# untitled.net
KiCad netlist of a schematic drawn in EAGLE
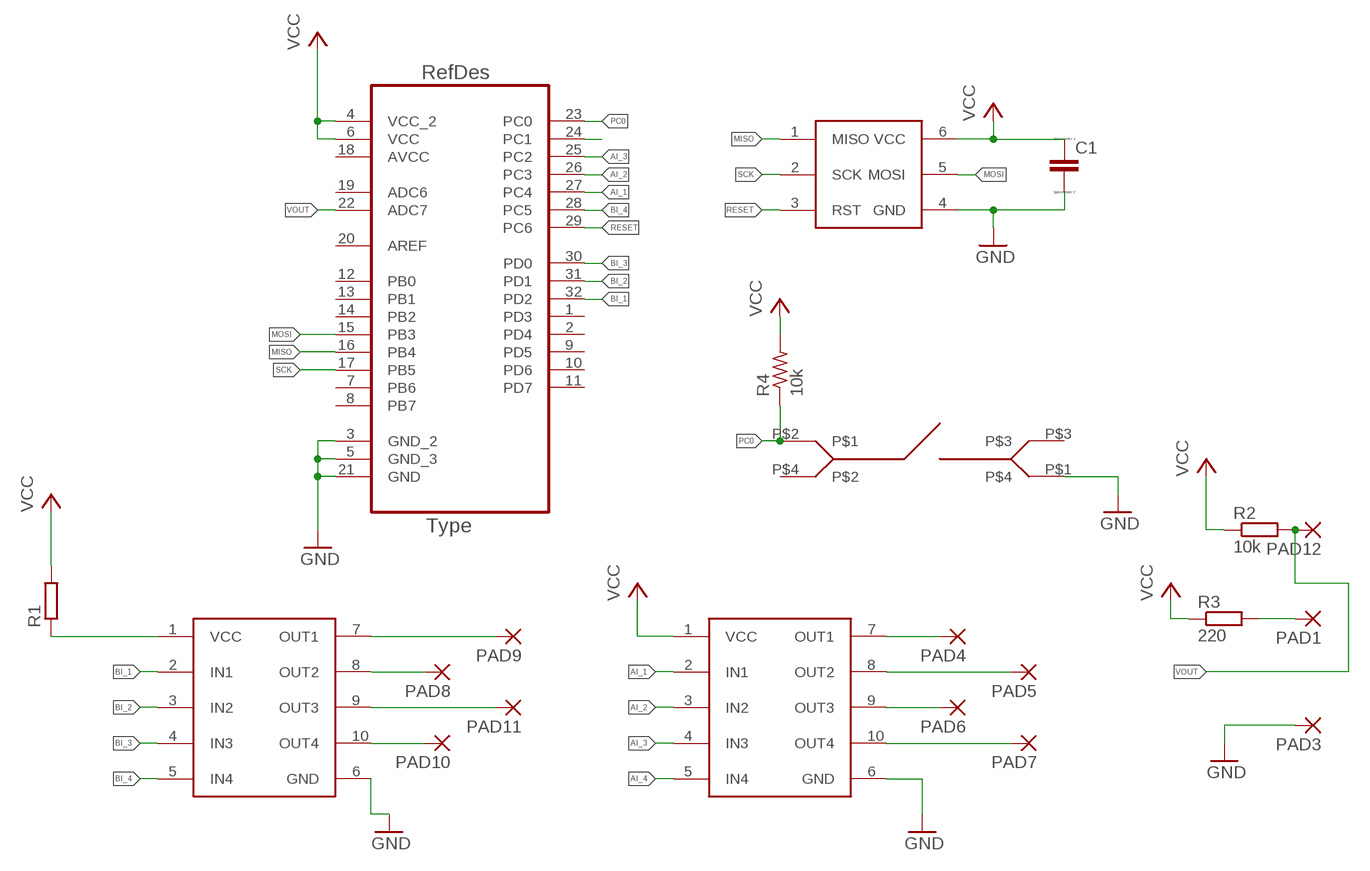
[diagram p0: schematic, sheet 1]

(export (version "E")
  (design (tool "Eeschema 10.0.6"))
  (components
    (comp (ref "C1")
      (value "CC1206")
      (footprint "eagle-import:C1206")
      (libsource (lib "eagle-import") (part "CC1206"))
    )
    (comp (ref "PAD1")
      (value "SMD2")
      (footprint "eagle-import:SMD1,27-2,54")
      (libsource (lib "eagle-import") (part "SMD2"))
    )
    (comp (ref "PAD3")
      (value "SMD2")
      (footprint "eagle-import:SMD1,27-2,54")
      (libsource (lib "eagle-import") (part "SMD2"))
    )
    (comp (ref "PAD4")
      (value "SMD2")
      (footprint "eagle-import:SMD1,27-2,54")
      (libsource (lib "eagle-import") (part "SMD2"))
    )
    (comp (ref "PAD5")
      (value "SMD2")
      (footprint "eagle-import:SMD1,27-2,54")
      (libsource (lib "eagle-import") (part "SMD2"))
    )
    (comp (ref "PAD6")
      (value "SMD2")
      (footprint "eagle-import:SMD1,27-2,54")
      (libsource (lib "eagle-import") (part "SMD2"))
    )
    (comp (ref "PAD7")
      (value "SMD2")
      (footprint "eagle-import:SMD1,27-2,54")
      (libsource (lib "eagle-import") (part "SMD2"))
    )
    (comp (ref "PAD8")
      (value "SMD2")
      (footprint "eagle-import:SMD1,27-2,54")
      (libsource (lib "eagle-import") (part "SMD2"))
    )
    (comp (ref "PAD9")
      (value "SMD2")
      (footprint "eagle-import:SMD1,27-2,54")
      (libsource (lib "eagle-import") (part "SMD2"))
    )
    (comp (ref "PAD10")
      (value "SMD2")
      (footprint "eagle-import:SMD1,27-2,54")
      (libsource (lib "eagle-import") (part "SMD2"))
    )
    (comp (ref "PAD11")
      (value "SMD2")
      (footprint "eagle-import:SMD1,27-2,54")
      (libsource (lib "eagle-import") (part "SMD2"))
    )
    (comp (ref "PAD12")
      (value "SMD2")
      (footprint "eagle-import:SMD1,27-2,54")
      (libsource (lib "eagle-import") (part "SMD2"))
    )
    (comp (ref "R1")
      (value "R-EU_M1206")
      (footprint "eagle-import:M1206")
      (libsource (lib "eagle-import") (part "R-EU_M1206"))
    )
    (comp (ref "R2")
      (value "10k")
      (footprint "eagle-import:M0805")
      (libsource (lib "eagle-import") (part "R-EU_M0805"))
    )
    (comp (ref "R3")
      (value "220")
      (footprint "eagle-import:M0805")
      (libsource (lib "eagle-import") (part "R-EU_M0805"))
    )
    (comp (ref "R4")
      (value "10k")
      (footprint "eagle-import:M0805")
      (libsource (lib "eagle-import") (part "R-US_M0805"))
    )
    (comp (ref "U$1")
      (value "LB1948MC_STEP_DRIVE")
      (footprint "eagle-import:SOIC_10")
      (libsource (lib "eagle-import") (part "LB1948MC_STEP_DRIVE"))
    )
    (comp (ref "U$2")
      (value "LB1948MC_STEP_DRIVE")
      (footprint "eagle-import:SOIC_10")
      (libsource (lib "eagle-import") (part "LB1948MC_STEP_DRIVE"))
    )
    (comp (ref "U$3")
      (value "2X6_AVR_HEADER")
      (footprint "eagle-import:2X6_AVR_PIN_HEADER_SMD")
      (libsource (lib "eagle-import") (part "2X6_AVR_HEADER"))
    )
    (comp (ref "U$4")
      (value "SMD_TACTILE_SWITCH")
      (footprint "eagle-import:SMD_TACTILE")
      (libsource (lib "eagle-import") (part "SMD_TACTILE_SWITCH"))
    )
    (comp (ref "U1")
      (value "ATMEGA328P-AU")
      (footprint "eagle-import:QFP80P900X900X120-32N")
      (libsource (lib "eagle-import") (part "ATMEGA328P-AU"))
    )
  )
  (nets
    (net (code "1") (name "/AVCC") (class "Default")
      (node (ref "U1") (pin "18") (pinfunction "AVCC_18") (pintype "power_in"))
    )
    (net (code "2") (name "AI_1") (class "Default")
      (node (ref "U$2") (pin "2") (pinfunction "IN1_2") (pintype "bidirectional"))
      (node (ref "U1") (pin "27") (pinfunction "PC4_27") (pintype "bidirectional"))
    )
    (net (code "3") (name "AI_2") (class "Default")
      (node (ref "U$2") (pin "3") (pinfunction "IN2_3") (pintype "bidirectional"))
      (node (ref "U1") (pin "26") (pinfunction "PC3_26") (pintype "bidirectional"))
    )
    (net (code "4") (name "AI_3") (class "Default")
      (node (ref "U$2") (pin "4") (pinfunction "IN3_4") (pintype "bidirectional"))
      (node (ref "U1") (pin "25") (pinfunction "PC2_25") (pintype "bidirectional"))
    )
    (net (code "5") (name "AI_4") (class "Default")
      (node (ref "U$2") (pin "5") (pinfunction "IN4_5") (pintype "bidirectional"))
      (node (ref "U1") (pin "24") (pinfunction "PC1_24") (pintype "bidirectional"))
    )
    (net (code "6") (name "BI_1") (class "Default")
      (node (ref "U$1") (pin "2") (pinfunction "IN1_2") (pintype "bidirectional"))
      (node (ref "U1") (pin "32") (pinfunction "PD2_32") (pintype "bidirectional"))
    )
    (net (code "7") (name "BI_2") (class "Default")
      (node (ref "U$1") (pin "3") (pinfunction "IN2_3") (pintype "bidirectional"))
      (node (ref "U1") (pin "31") (pinfunction "PD1_31") (pintype "bidirectional"))
    )
    (net (code "8") (name "BI_3") (class "Default")
      (node (ref "U$1") (pin "4") (pinfunction "IN3_4") (pintype "bidirectional"))
      (node (ref "U1") (pin "30") (pinfunction "PD0_30") (pintype "bidirectional"))
    )
    (net (code "9") (name "BI_4") (class "Default")
      (node (ref "U$1") (pin "5") (pinfunction "IN4_5") (pintype "bidirectional"))
      (node (ref "U1") (pin "28") (pinfunction "PC5_28") (pintype "bidirectional"))
    )
    (net (code "10") (name "GND") (class "Default")
      (node (ref "C1") (pin "2") (pinfunction "2_2") (pintype "passive"))
      (node (ref "PAD3") (pin "1") (pinfunction "P_1") (pintype "passive"))
      (node (ref "U$1") (pin "6") (pinfunction "GND_6") (pintype "bidirectional"))
      (node (ref "U$2") (pin "6") (pinfunction "GND_6") (pintype "bidirectional"))
      (node (ref "U$3") (pin "4") (pinfunction "GND_4") (pintype "bidirectional"))
      (node (ref "U$4") (pin "P$1") (pinfunction "P$4_P$1") (pintype "bidirectional"))
      (node (ref "U1") (pin "21") (pinfunction "GND_21") (pintype "passive"))
      (node (ref "U1") (pin "3") (pinfunction "GND_2_3") (pintype "passive"))
      (node (ref "U1") (pin "5") (pinfunction "GND_3_5") (pintype "passive"))
    )
    (net (code "11") (name "MISO") (class "Default")
      (node (ref "U$3") (pin "1") (pinfunction "MISO_1") (pintype "bidirectional"))
      (node (ref "U1") (pin "16") (pinfunction "PB4_16") (pintype "bidirectional"))
    )
    (net (code "12") (name "MOSI") (class "Default")
      (node (ref "U$3") (pin "5") (pinfunction "MOSI_5") (pintype "bidirectional"))
      (node (ref "U1") (pin "15") (pinfunction "PB3_15") (pintype "bidirectional"))
    )
    (net (code "13") (name "Net-(PAD1-P)") (class "Default")
      (node (ref "PAD1") (pin "1") (pinfunction "P_1") (pintype "passive"))
      (node (ref "R3") (pin "2") (pinfunction "2_2") (pintype "passive"))
    )
    (net (code "14") (name "Net-(PAD4-P)") (class "Default")
      (node (ref "PAD4") (pin "1") (pinfunction "P_1") (pintype "passive"))
      (node (ref "U$2") (pin "7") (pinfunction "OUT1_7") (pintype "bidirectional"))
    )
    (net (code "15") (name "Net-(PAD5-P)") (class "Default")
      (node (ref "PAD5") (pin "1") (pinfunction "P_1") (pintype "passive"))
      (node (ref "U$2") (pin "8") (pinfunction "OUT2_8") (pintype "bidirectional"))
    )
    (net (code "16") (name "Net-(PAD6-P)") (class "Default")
      (node (ref "PAD6") (pin "1") (pinfunction "P_1") (pintype "passive"))
      (node (ref "U$2") (pin "9") (pinfunction "OUT3_9") (pintype "bidirectional"))
    )
    (net (code "17") (name "Net-(PAD7-P)") (class "Default")
      (node (ref "PAD7") (pin "1") (pinfunction "P_1") (pintype "passive"))
      (node (ref "U$2") (pin "10") (pinfunction "OUT4_10") (pintype "bidirectional"))
    )
    (net (code "18") (name "Net-(PAD8-P)") (class "Default")
      (node (ref "PAD8") (pin "1") (pinfunction "P_1") (pintype "passive"))
      (node (ref "U$1") (pin "8") (pinfunction "OUT2_8") (pintype "bidirectional"))
    )
    (net (code "19") (name "Net-(PAD9-P)") (class "Default")
      (node (ref "PAD9") (pin "1") (pinfunction "P_1") (pintype "passive"))
      (node (ref "U$1") (pin "7") (pinfunction "OUT1_7") (pintype "bidirectional"))
    )
    (net (code "20") (name "Net-(PAD10-P)") (class "Default")
      (node (ref "PAD10") (pin "1") (pinfunction "P_1") (pintype "passive"))
      (node (ref "U$1") (pin "10") (pinfunction "OUT4_10") (pintype "bidirectional"))
    )
    (net (code "21") (name "Net-(PAD11-P)") (class "Default")
      (node (ref "PAD11") (pin "1") (pinfunction "P_1") (pintype "passive"))
      (node (ref "U$1") (pin "9") (pinfunction "OUT3_9") (pintype "bidirectional"))
    )
    (net (code "22") (name "Net-(U$1-VCC)") (class "Default")
      (node (ref "R1") (pin "1") (pinfunction "1_1") (pintype "passive"))
      (node (ref "U$1") (pin "1") (pinfunction "VCC_1") (pintype "bidirectional"))
    )
    (net (code "23") (name "PC0") (class "Default")
      (node (ref "R4") (pin "1") (pinfunction "1_1") (pintype "passive"))
      (node (ref "U$4") (pin "P$2") (pinfunction "P$1_P$2") (pintype "bidirectional"))
      (node (ref "U1") (pin "23") (pinfunction "PC0_23") (pintype "bidirectional"))
    )
    (net (code "24") (name "RESET") (class "Default")
      (node (ref "U$3") (pin "3") (pinfunction "RST_3") (pintype "bidirectional"))
      (node (ref "U1") (pin "29") (pinfunction "PC6_29") (pintype "bidirectional"))
    )
    (net (code "25") (name "SCK") (class "Default")
      (node (ref "U$3") (pin "2") (pinfunction "SCK_2") (pintype "bidirectional"))
      (node (ref "U1") (pin "17") (pinfunction "PB5_17") (pintype "bidirectional"))
    )
    (net (code "26") (name "VCC") (class "Default")
      (node (ref "C1") (pin "1") (pinfunction "1_1") (pintype "passive"))
      (node (ref "R1") (pin "2") (pinfunction "2_2") (pintype "passive"))
      (node (ref "R2") (pin "1") (pinfunction "1_1") (pintype "passive"))
      (node (ref "R3") (pin "1") (pinfunction "1_1") (pintype "passive"))
      (node (ref "R4") (pin "2") (pinfunction "2_2") (pintype "passive"))
      (node (ref "U$2") (pin "1") (pinfunction "VCC_1") (pintype "bidirectional"))
      (node (ref "U$3") (pin "6") (pinfunction "VCC_6") (pintype "bidirectional"))
      (node (ref "U1") (pin "4") (pinfunction "VCC_2_4") (pintype "power_in"))
      (node (ref "U1") (pin "6") (pinfunction "VCC_6") (pintype "power_in"))
    )
    (net (code "27") (name "VOUT") (class "Default")
      (node (ref "PAD12") (pin "1") (pinfunction "P_1") (pintype "passive"))
      (node (ref "R2") (pin "2") (pinfunction "2_2") (pintype "passive"))
      (node (ref "U1") (pin "22") (pinfunction "ADC7_22") (pintype "input"))
    )
    (net (code "28") (name "unconnected-(U$4-P$2-PadP$4)") (class "Default")
      (node (ref "U$4") (pin "P$4") (pinfunction "P$2_P$4") (pintype "bidirectional"))
    )
    (net (code "29") (name "unconnected-(U$4-PadP$3)") (class "Default")
      (node (ref "U$4") (pin "P$3") (pinfunction "P$3_P$3") (pintype "bidirectional"))
    )
    (net (code "30") (name "unconnected-(U1-ADC6-Pad19)") (class "Default")
      (node (ref "U1") (pin "19") (pinfunction "ADC6_19") (pintype "input"))
    )
    (net (code "31") (name "unconnected-(U1-AREF-Pad20)") (class "Default")
      (node (ref "U1") (pin "20") (pinfunction "AREF_20") (pintype "input"))
    )
    (net (code "32") (name "unconnected-(U1-PB0-Pad12)") (class "Default")
      (node (ref "U1") (pin "12") (pinfunction "PB0_12") (pintype "bidirectional"))
    )
    (net (code "33") (name "unconnected-(U1-PB1-Pad13)") (class "Default")
      (node (ref "U1") (pin "13") (pinfunction "PB1_13") (pintype "bidirectional"))
    )
    (net (code "34") (name "unconnected-(U1-PB2-Pad14)") (class "Default")
      (node (ref "U1") (pin "14") (pinfunction "PB2_14") (pintype "bidirectional"))
    )
    (net (code "35") (name "unconnected-(U1-PB6-Pad7)") (class "Default")
      (node (ref "U1") (pin "7") (pinfunction "PB6_7") (pintype "bidirectional"))
    )
    (net (code "36") (name "unconnected-(U1-PB7-Pad8)") (class "Default")
      (node (ref "U1") (pin "8") (pinfunction "PB7_8") (pintype "bidirectional"))
    )
    (net (code "37") (name "unconnected-(U1-PD3-Pad1)") (class "Default")
      (node (ref "U1") (pin "1") (pinfunction "PD3_1") (pintype "bidirectional"))
    )
    (net (code "38") (name "unconnected-(U1-PD4-Pad2)") (class "Default")
      (node (ref "U1") (pin "2") (pinfunction "PD4_2") (pintype "bidirectional"))
    )
    (net (code "39") (name "unconnected-(U1-PD5-Pad9)") (class "Default")
      (node (ref "U1") (pin "9") (pinfunction "PD5_9") (pintype "bidirectional"))
    )
    (net (code "40") (name "unconnected-(U1-PD6-Pad10)") (class "Default")
      (node (ref "U1") (pin "10") (pinfunction "PD6_10") (pintype "bidirectional"))
    )
    (net (code "41") (name "unconnected-(U1-PD7-Pad11)") (class "Default")
      (node (ref "U1") (pin "11") (pinfunction "PD7_11") (pintype "bidirectional"))
    )
  )
)
